# main.net
KiCad netlist of a schematic drawn in Altium Designer
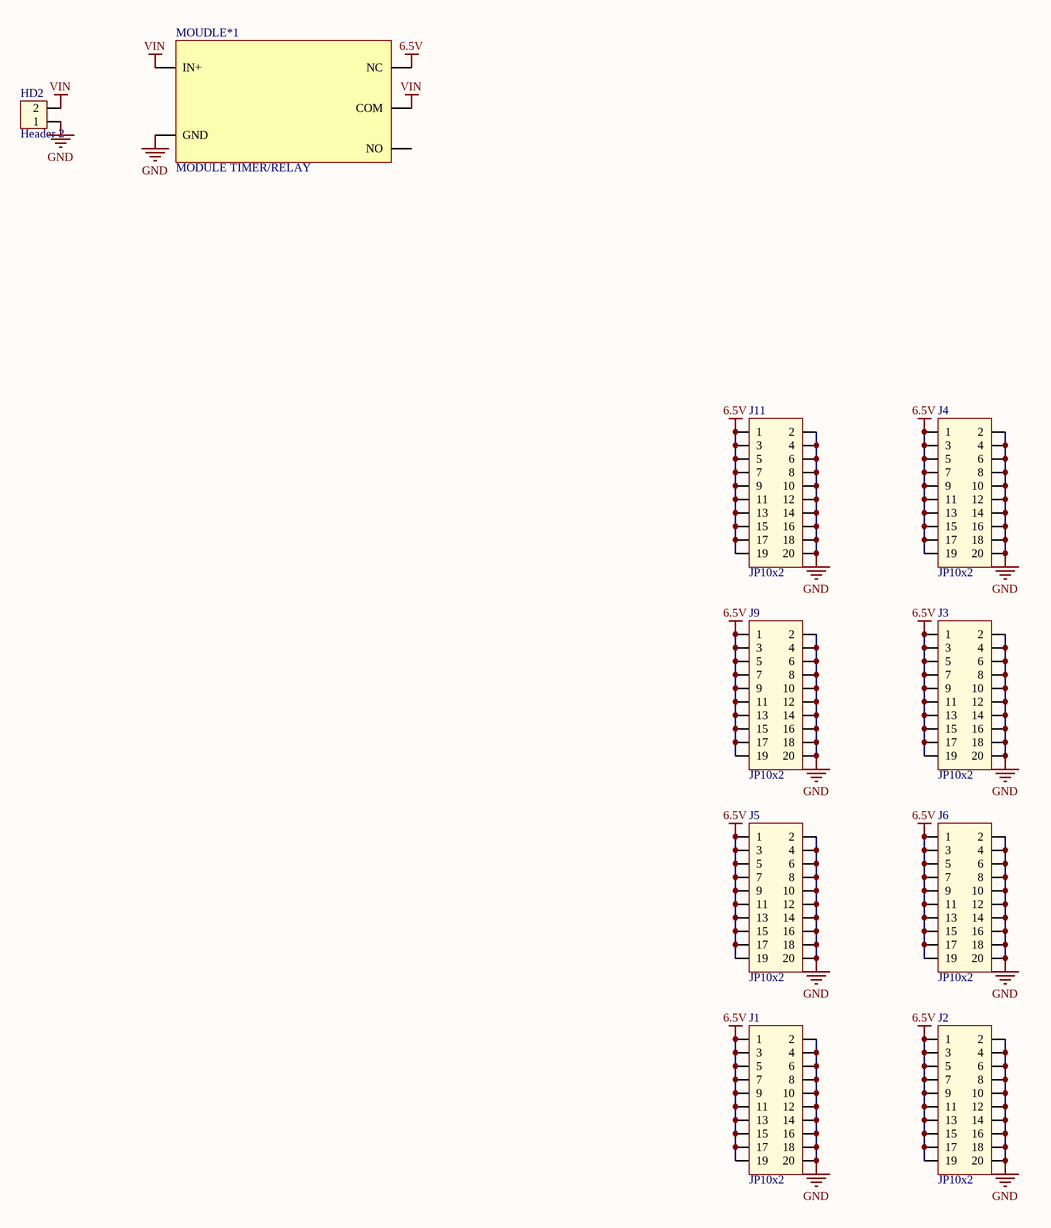
[diagram p0: main.SchDoc]

(export (version "E")
  (design (tool "Eeschema 10.0.6"))
  (components
    (comp (ref "HD2")
      (value "Header 2")
      (footprint "HED2 -C")
      (description "Header 2 (Green)")
      (libsource (lib "hanguyen") (part "Hed2"))
    )
    (comp (ref "J1")
      (value "JP10x2")
      (footprint "JP10x2 - duplicate")
      (libsource (lib "hanguyen") (part "JP10x2"))
    )
    (comp (ref "J2")
      (value "JP10x2")
      (footprint "JP10x2 - duplicate")
      (libsource (lib "hanguyen") (part "JP10x2"))
    )
    (comp (ref "J3")
      (value "JP10x2")
      (footprint "JP10x2 - duplicate")
      (libsource (lib "hanguyen") (part "JP10x2"))
    )
    (comp (ref "J4")
      (value "JP10x2")
      (footprint "JP10x2 - duplicate")
      (libsource (lib "hanguyen") (part "JP10x2"))
    )
    (comp (ref "J5")
      (value "JP10x2")
      (footprint "JP10x2 - duplicate")
      (libsource (lib "hanguyen") (part "JP10x2"))
    )
    (comp (ref "J6")
      (value "JP10x2")
      (footprint "JP10x2 - duplicate")
      (libsource (lib "hanguyen") (part "JP10x2"))
    )
    (comp (ref "J9")
      (value "JP10x2")
      (footprint "JP10x2 - duplicate")
      (libsource (lib "hanguyen") (part "JP10x2"))
    )
    (comp (ref "J11")
      (value "JP10x2")
      (footprint "JP10x2 - duplicate")
      (libsource (lib "hanguyen") (part "JP10x2"))
    )
    (comp (ref "MOUDLE*1")
      (value "MODULE TIMER/RELAY")
      (footprint "MODULE TIMER/RELAY")
      (libsource (lib "Schlib1") (part "MODULE TIMER/RELAY"))
    )
  )
  (nets
    (net (code "1") (name "6.5V") (class "Default")
      (node (ref "J1") (pin "1") (pinfunction "1_1") (pintype "passive"))
      (node (ref "J1") (pin "11") (pinfunction "11_11") (pintype "passive"))
      (node (ref "J1") (pin "13") (pinfunction "13_13") (pintype "passive"))
      (node (ref "J1") (pin "15") (pinfunction "15_15") (pintype "passive"))
      (node (ref "J1") (pin "17") (pinfunction "17_17") (pintype "passive"))
      (node (ref "J1") (pin "19") (pinfunction "19_19") (pintype "passive"))
      (node (ref "J1") (pin "3") (pinfunction "3_3") (pintype "passive"))
      (node (ref "J1") (pin "5") (pinfunction "5_5") (pintype "passive"))
      (node (ref "J1") (pin "7") (pinfunction "7_7") (pintype "passive"))
      (node (ref "J1") (pin "9") (pinfunction "9_9") (pintype "passive"))
      (node (ref "J11") (pin "1") (pinfunction "1_1") (pintype "passive"))
      (node (ref "J11") (pin "11") (pinfunction "11_11") (pintype "passive"))
      (node (ref "J11") (pin "13") (pinfunction "13_13") (pintype "passive"))
      (node (ref "J11") (pin "15") (pinfunction "15_15") (pintype "passive"))
      (node (ref "J11") (pin "17") (pinfunction "17_17") (pintype "passive"))
      (node (ref "J11") (pin "19") (pinfunction "19_19") (pintype "passive"))
      (node (ref "J11") (pin "3") (pinfunction "3_3") (pintype "passive"))
      (node (ref "J11") (pin "5") (pinfunction "5_5") (pintype "passive"))
      (node (ref "J11") (pin "7") (pinfunction "7_7") (pintype "passive"))
      (node (ref "J11") (pin "9") (pinfunction "9_9") (pintype "passive"))
      (node (ref "J2") (pin "1") (pinfunction "1_1") (pintype "passive"))
      (node (ref "J2") (pin "11") (pinfunction "11_11") (pintype "passive"))
      (node (ref "J2") (pin "13") (pinfunction "13_13") (pintype "passive"))
      (node (ref "J2") (pin "15") (pinfunction "15_15") (pintype "passive"))
      (node (ref "J2") (pin "17") (pinfunction "17_17") (pintype "passive"))
      (node (ref "J2") (pin "19") (pinfunction "19_19") (pintype "passive"))
      (node (ref "J2") (pin "3") (pinfunction "3_3") (pintype "passive"))
      (node (ref "J2") (pin "5") (pinfunction "5_5") (pintype "passive"))
      (node (ref "J2") (pin "7") (pinfunction "7_7") (pintype "passive"))
      (node (ref "J2") (pin "9") (pinfunction "9_9") (pintype "passive"))
      (node (ref "J3") (pin "1") (pinfunction "1_1") (pintype "passive"))
      (node (ref "J3") (pin "11") (pinfunction "11_11") (pintype "passive"))
      (node (ref "J3") (pin "13") (pinfunction "13_13") (pintype "passive"))
      (node (ref "J3") (pin "15") (pinfunction "15_15") (pintype "passive"))
      (node (ref "J3") (pin "17") (pinfunction "17_17") (pintype "passive"))
      (node (ref "J3") (pin "19") (pinfunction "19_19") (pintype "passive"))
      (node (ref "J3") (pin "3") (pinfunction "3_3") (pintype "passive"))
      (node (ref "J3") (pin "5") (pinfunction "5_5") (pintype "passive"))
      (node (ref "J3") (pin "7") (pinfunction "7_7") (pintype "passive"))
      (node (ref "J3") (pin "9") (pinfunction "9_9") (pintype "passive"))
      (node (ref "J4") (pin "1") (pinfunction "1_1") (pintype "passive"))
      (node (ref "J4") (pin "11") (pinfunction "11_11") (pintype "passive"))
      (node (ref "J4") (pin "13") (pinfunction "13_13") (pintype "passive"))
      (node (ref "J4") (pin "15") (pinfunction "15_15") (pintype "passive"))
      (node (ref "J4") (pin "17") (pinfunction "17_17") (pintype "passive"))
      (node (ref "J4") (pin "19") (pinfunction "19_19") (pintype "passive"))
      (node (ref "J4") (pin "3") (pinfunction "3_3") (pintype "passive"))
      (node (ref "J4") (pin "5") (pinfunction "5_5") (pintype "passive"))
      (node (ref "J4") (pin "7") (pinfunction "7_7") (pintype "passive"))
      (node (ref "J4") (pin "9") (pinfunction "9_9") (pintype "passive"))
      (node (ref "J5") (pin "1") (pinfunction "1_1") (pintype "passive"))
      (node (ref "J5") (pin "11") (pinfunction "11_11") (pintype "passive"))
      (node (ref "J5") (pin "13") (pinfunction "13_13") (pintype "passive"))
      (node (ref "J5") (pin "15") (pinfunction "15_15") (pintype "passive"))
      (node (ref "J5") (pin "17") (pinfunction "17_17") (pintype "passive"))
      (node (ref "J5") (pin "19") (pinfunction "19_19") (pintype "passive"))
      (node (ref "J5") (pin "3") (pinfunction "3_3") (pintype "passive"))
      (node (ref "J5") (pin "5") (pinfunction "5_5") (pintype "passive"))
      (node (ref "J5") (pin "7") (pinfunction "7_7") (pintype "passive"))
      (node (ref "J5") (pin "9") (pinfunction "9_9") (pintype "passive"))
      (node (ref "J6") (pin "1") (pinfunction "1_1") (pintype "passive"))
      (node (ref "J6") (pin "11") (pinfunction "11_11") (pintype "passive"))
      (node (ref "J6") (pin "13") (pinfunction "13_13") (pintype "passive"))
      (node (ref "J6") (pin "15") (pinfunction "15_15") (pintype "passive"))
      (node (ref "J6") (pin "17") (pinfunction "17_17") (pintype "passive"))
      (node (ref "J6") (pin "19") (pinfunction "19_19") (pintype "passive"))
      (node (ref "J6") (pin "3") (pinfunction "3_3") (pintype "passive"))
      (node (ref "J6") (pin "5") (pinfunction "5_5") (pintype "passive"))
      (node (ref "J6") (pin "7") (pinfunction "7_7") (pintype "passive"))
      (node (ref "J6") (pin "9") (pinfunction "9_9") (pintype "passive"))
      (node (ref "J9") (pin "1") (pinfunction "1_1") (pintype "passive"))
      (node (ref "J9") (pin "11") (pinfunction "11_11") (pintype "passive"))
      (node (ref "J9") (pin "13") (pinfunction "13_13") (pintype "passive"))
      (node (ref "J9") (pin "15") (pinfunction "15_15") (pintype "passive"))
      (node (ref "J9") (pin "17") (pinfunction "17_17") (pintype "passive"))
      (node (ref "J9") (pin "19") (pinfunction "19_19") (pintype "passive"))
      (node (ref "J9") (pin "3") (pinfunction "3_3") (pintype "passive"))
      (node (ref "J9") (pin "5") (pinfunction "5_5") (pintype "passive"))
      (node (ref "J9") (pin "7") (pinfunction "7_7") (pintype "passive"))
      (node (ref "J9") (pin "9") (pinfunction "9_9") (pintype "passive"))
      (node (ref "MOUDLE*1") (pin "NC") (pinfunction "NC_NC") (pintype "passive"))
    )
    (net (code "2") (name "GND") (class "Default")
      (node (ref "HD2") (pin "1") (pinfunction "1_1") (pintype "passive"))
      (node (ref "J1") (pin "10") (pinfunction "10_10") (pintype "passive"))
      (node (ref "J1") (pin "12") (pinfunction "12_12") (pintype "passive"))
      (node (ref "J1") (pin "14") (pinfunction "14_14") (pintype "passive"))
      (node (ref "J1") (pin "16") (pinfunction "16_16") (pintype "passive"))
      (node (ref "J1") (pin "18") (pinfunction "18_18") (pintype "passive"))
      (node (ref "J1") (pin "2") (pinfunction "2_2") (pintype "passive"))
      (node (ref "J1") (pin "20") (pinfunction "20_20") (pintype "passive"))
      (node (ref "J1") (pin "4") (pinfunction "4_4") (pintype "passive"))
      (node (ref "J1") (pin "6") (pinfunction "6_6") (pintype "passive"))
      (node (ref "J1") (pin "8") (pinfunction "8_8") (pintype "passive"))
      (node (ref "J11") (pin "10") (pinfunction "10_10") (pintype "passive"))
      (node (ref "J11") (pin "12") (pinfunction "12_12") (pintype "passive"))
      (node (ref "J11") (pin "14") (pinfunction "14_14") (pintype "passive"))
      (node (ref "J11") (pin "16") (pinfunction "16_16") (pintype "passive"))
      (node (ref "J11") (pin "18") (pinfunction "18_18") (pintype "passive"))
      (node (ref "J11") (pin "2") (pinfunction "2_2") (pintype "passive"))
      (node (ref "J11") (pin "20") (pinfunction "20_20") (pintype "passive"))
      (node (ref "J11") (pin "4") (pinfunction "4_4") (pintype "passive"))
      (node (ref "J11") (pin "6") (pinfunction "6_6") (pintype "passive"))
      (node (ref "J11") (pin "8") (pinfunction "8_8") (pintype "passive"))
      (node (ref "J2") (pin "10") (pinfunction "10_10") (pintype "passive"))
      (node (ref "J2") (pin "12") (pinfunction "12_12") (pintype "passive"))
      (node (ref "J2") (pin "14") (pinfunction "14_14") (pintype "passive"))
      (node (ref "J2") (pin "16") (pinfunction "16_16") (pintype "passive"))
      (node (ref "J2") (pin "18") (pinfunction "18_18") (pintype "passive"))
      (node (ref "J2") (pin "2") (pinfunction "2_2") (pintype "passive"))
      (node (ref "J2") (pin "20") (pinfunction "20_20") (pintype "passive"))
      (node (ref "J2") (pin "4") (pinfunction "4_4") (pintype "passive"))
      (node (ref "J2") (pin "6") (pinfunction "6_6") (pintype "passive"))
      (node (ref "J2") (pin "8") (pinfunction "8_8") (pintype "passive"))
      (node (ref "J3") (pin "10") (pinfunction "10_10") (pintype "passive"))
      (node (ref "J3") (pin "12") (pinfunction "12_12") (pintype "passive"))
      (node (ref "J3") (pin "14") (pinfunction "14_14") (pintype "passive"))
      (node (ref "J3") (pin "16") (pinfunction "16_16") (pintype "passive"))
      (node (ref "J3") (pin "18") (pinfunction "18_18") (pintype "passive"))
      (node (ref "J3") (pin "2") (pinfunction "2_2") (pintype "passive"))
      (node (ref "J3") (pin "20") (pinfunction "20_20") (pintype "passive"))
      (node (ref "J3") (pin "4") (pinfunction "4_4") (pintype "passive"))
      (node (ref "J3") (pin "6") (pinfunction "6_6") (pintype "passive"))
      (node (ref "J3") (pin "8") (pinfunction "8_8") (pintype "passive"))
      (node (ref "J4") (pin "10") (pinfunction "10_10") (pintype "passive"))
      (node (ref "J4") (pin "12") (pinfunction "12_12") (pintype "passive"))
      (node (ref "J4") (pin "14") (pinfunction "14_14") (pintype "passive"))
      (node (ref "J4") (pin "16") (pinfunction "16_16") (pintype "passive"))
      (node (ref "J4") (pin "18") (pinfunction "18_18") (pintype "passive"))
      (node (ref "J4") (pin "2") (pinfunction "2_2") (pintype "passive"))
      (node (ref "J4") (pin "20") (pinfunction "20_20") (pintype "passive"))
      (node (ref "J4") (pin "4") (pinfunction "4_4") (pintype "passive"))
      (node (ref "J4") (pin "6") (pinfunction "6_6") (pintype "passive"))
      (node (ref "J4") (pin "8") (pinfunction "8_8") (pintype "passive"))
      (node (ref "J5") (pin "10") (pinfunction "10_10") (pintype "passive"))
      (node (ref "J5") (pin "12") (pinfunction "12_12") (pintype "passive"))
      (node (ref "J5") (pin "14") (pinfunction "14_14") (pintype "passive"))
      (node (ref "J5") (pin "16") (pinfunction "16_16") (pintype "passive"))
      (node (ref "J5") (pin "18") (pinfunction "18_18") (pintype "passive"))
      (node (ref "J5") (pin "2") (pinfunction "2_2") (pintype "passive"))
      (node (ref "J5") (pin "20") (pinfunction "20_20") (pintype "passive"))
      (node (ref "J5") (pin "4") (pinfunction "4_4") (pintype "passive"))
      (node (ref "J5") (pin "6") (pinfunction "6_6") (pintype "passive"))
      (node (ref "J5") (pin "8") (pinfunction "8_8") (pintype "passive"))
      (node (ref "J6") (pin "10") (pinfunction "10_10") (pintype "passive"))
      (node (ref "J6") (pin "12") (pinfunction "12_12") (pintype "passive"))
      (node (ref "J6") (pin "14") (pinfunction "14_14") (pintype "passive"))
      (node (ref "J6") (pin "16") (pinfunction "16_16") (pintype "passive"))
      (node (ref "J6") (pin "18") (pinfunction "18_18") (pintype "passive"))
      (node (ref "J6") (pin "2") (pinfunction "2_2") (pintype "passive"))
      (node (ref "J6") (pin "20") (pinfunction "20_20") (pintype "passive"))
      (node (ref "J6") (pin "4") (pinfunction "4_4") (pintype "passive"))
      (node (ref "J6") (pin "6") (pinfunction "6_6") (pintype "passive"))
      (node (ref "J6") (pin "8") (pinfunction "8_8") (pintype "passive"))
      (node (ref "J9") (pin "10") (pinfunction "10_10") (pintype "passive"))
      (node (ref "J9") (pin "12") (pinfunction "12_12") (pintype "passive"))
      (node (ref "J9") (pin "14") (pinfunction "14_14") (pintype "passive"))
      (node (ref "J9") (pin "16") (pinfunction "16_16") (pintype "passive"))
      (node (ref "J9") (pin "18") (pinfunction "18_18") (pintype "passive"))
      (node (ref "J9") (pin "2") (pinfunction "2_2") (pintype "passive"))
      (node (ref "J9") (pin "20") (pinfunction "20_20") (pintype "passive"))
      (node (ref "J9") (pin "4") (pinfunction "4_4") (pintype "passive"))
      (node (ref "J9") (pin "6") (pinfunction "6_6") (pintype "passive"))
      (node (ref "J9") (pin "8") (pinfunction "8_8") (pintype "passive"))
      (node (ref "MOUDLE*1") (pin "GND") (pinfunction "GND_GND") (pintype "passive"))
    )
    (net (code "3") (name "VIN") (class "Default")
      (node (ref "HD2") (pin "2") (pinfunction "2_2") (pintype "passive"))
      (node (ref "MOUDLE*1") (pin "COM") (pinfunction "COM_COM") (pintype "passive"))
      (node (ref "MOUDLE*1") (pin "IN+") (pinfunction "IN+_IN+") (pintype "passive"))
    )
    (net (code "4") (name "unconnected-(MOUDLE*1-PadNO)") (class "Default")
      (node (ref "MOUDLE*1") (pin "NO") (pinfunction "NO_NO") (pintype "passive"))
    )
  )
)
